# display-bar.net
KiCad netlist of a schematic drawn in EAGLE
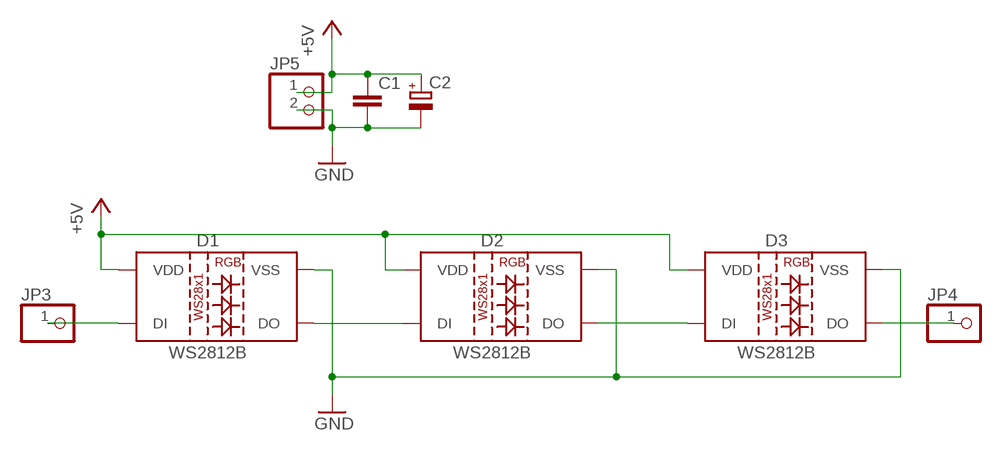
[diagram p0: schematic, sheet 1]

(export (version "E")
  (design (tool "Eeschema 10.0.6"))
  (components
    (comp (ref "C1")
      (value "C-EUC1206")
      (footprint "eagle-import:C1206")
      (libsource (lib "eagle-import") (part "C-EUC1206"))
    )
    (comp (ref "C2")
      (value "CPOL-EUE2.5-6")
      (footprint "eagle-import:E2,5-6")
      (libsource (lib "eagle-import") (part "CPOL-EUE2.5-6"))
    )
    (comp (ref "D1")
      (value "WS2812B")
      (footprint "eagle-import:WS2812B")
      (fields (field (name "MF") "Worldsemi"))
      (libsource (lib "eagle-import") (part "WS2812B"))
    )
    (comp (ref "D2")
      (value "WS2812B")
      (footprint "eagle-import:WS2812B")
      (fields (field (name "MF") "Worldsemi"))
      (libsource (lib "eagle-import") (part "WS2812B"))
    )
    (comp (ref "D3")
      (value "WS2812B")
      (footprint "eagle-import:WS2812B")
      (fields (field (name "MF") "Worldsemi"))
      (libsource (lib "eagle-import") (part "WS2812B"))
    )
    (comp (ref "JP3")
      (value "PINHD-1X1")
      (footprint "eagle-import:1X01")
      (libsource (lib "eagle-import") (part "PINHD-1X1"))
    )
    (comp (ref "JP4")
      (value "PINHD-1X1")
      (footprint "eagle-import:1X01")
      (libsource (lib "eagle-import") (part "PINHD-1X1"))
    )
    (comp (ref "JP5")
      (value "PINHD-1X2")
      (footprint "eagle-import:1X02")
      (libsource (lib "eagle-import") (part "PINHD-1X2"))
    )
  )
  (nets
    (net (code "1") (name "+5V") (class "Default")
      (node (ref "C1") (pin "1") (pinfunction "1_1") (pintype "passive"))
      (node (ref "C2") (pin "+") (pinfunction "+_+") (pintype "passive"))
      (node (ref "D1") (pin "1") (pinfunction "VDD_1") (pintype "bidirectional"))
      (node (ref "D2") (pin "1") (pinfunction "VDD_1") (pintype "bidirectional"))
      (node (ref "D3") (pin "1") (pinfunction "VDD_1") (pintype "bidirectional"))
      (node (ref "JP5") (pin "1") (pinfunction "1_1") (pintype "passive"))
    )
    (net (code "2") (name "GND") (class "Default")
      (node (ref "C1") (pin "2") (pinfunction "2_2") (pintype "passive"))
      (node (ref "C2") (pin "-") (pinfunction "-_-") (pintype "passive"))
      (node (ref "D1") (pin "3") (pinfunction "VSS_3") (pintype "bidirectional"))
      (node (ref "D2") (pin "3") (pinfunction "VSS_3") (pintype "bidirectional"))
      (node (ref "D3") (pin "3") (pinfunction "VSS_3") (pintype "bidirectional"))
      (node (ref "JP5") (pin "2") (pinfunction "2_2") (pintype "passive"))
    )
    (net (code "3") (name "Net-(D1-DI)") (class "Default")
      (node (ref "D1") (pin "4") (pinfunction "DI_4") (pintype "bidirectional"))
      (node (ref "JP3") (pin "1") (pinfunction "1_1") (pintype "passive"))
    )
    (net (code "4") (name "Net-(D1-DO)") (class "Default")
      (node (ref "D1") (pin "2") (pinfunction "DO_2") (pintype "bidirectional"))
      (node (ref "D2") (pin "4") (pinfunction "DI_4") (pintype "bidirectional"))
    )
    (net (code "5") (name "Net-(D2-DO)") (class "Default")
      (node (ref "D2") (pin "2") (pinfunction "DO_2") (pintype "bidirectional"))
      (node (ref "D3") (pin "4") (pinfunction "DI_4") (pintype "bidirectional"))
    )
    (net (code "6") (name "Net-(D3-DO)") (class "Default")
      (node (ref "D3") (pin "2") (pinfunction "DO_2") (pintype "bidirectional"))
      (node (ref "JP4") (pin "1") (pinfunction "1_1") (pintype "passive"))
    )
  )
)
